# TEENSY_AUDIO_BOARDS.net
KiCad netlist of a schematic drawn in EAGLE
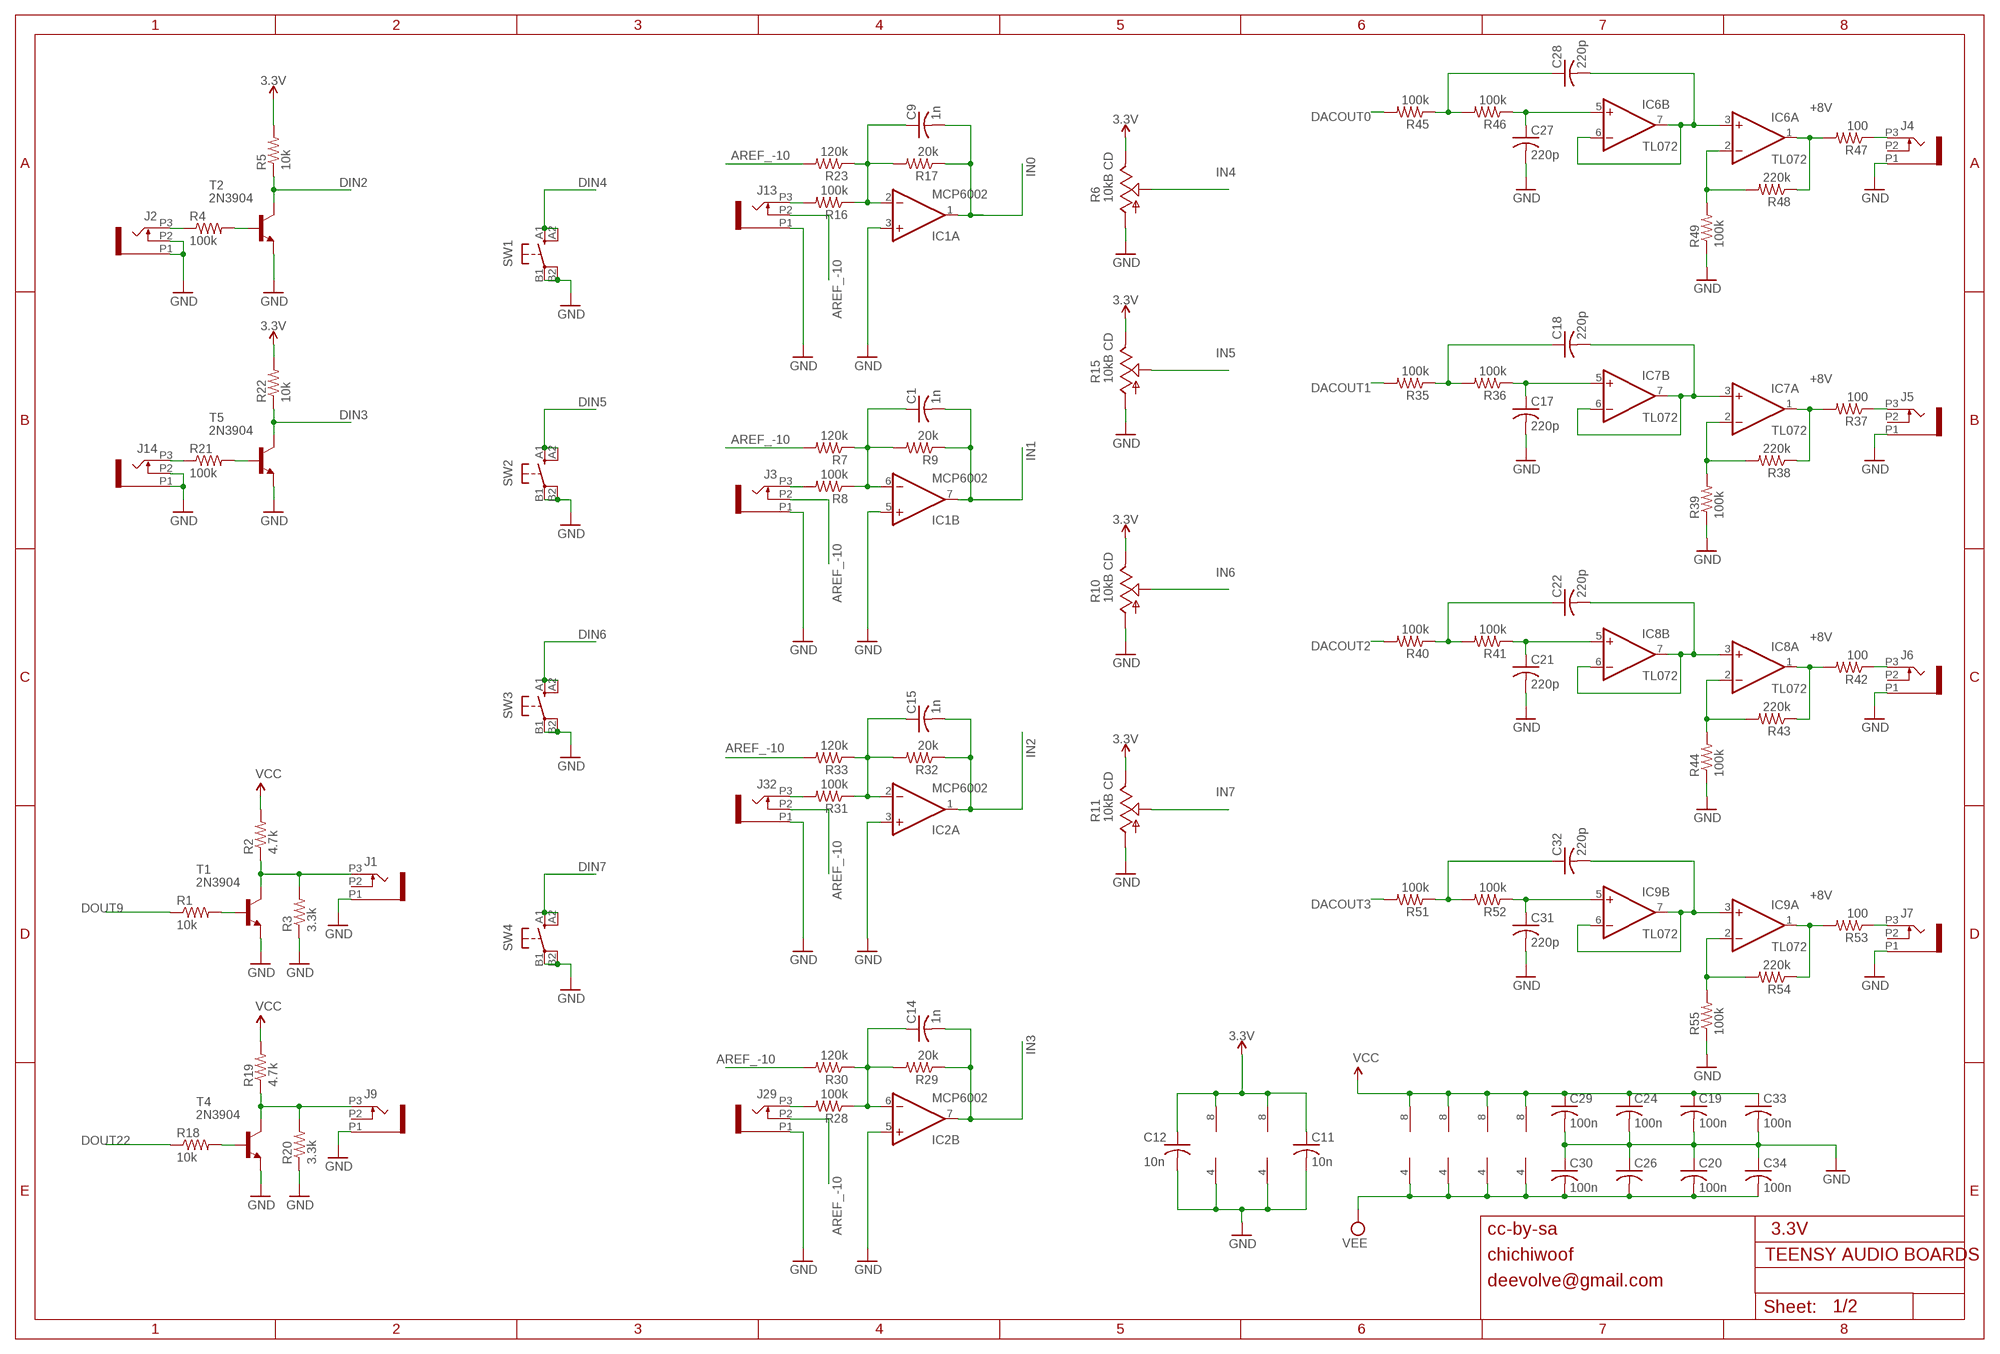
[diagram p0: schematic, sheet 1]
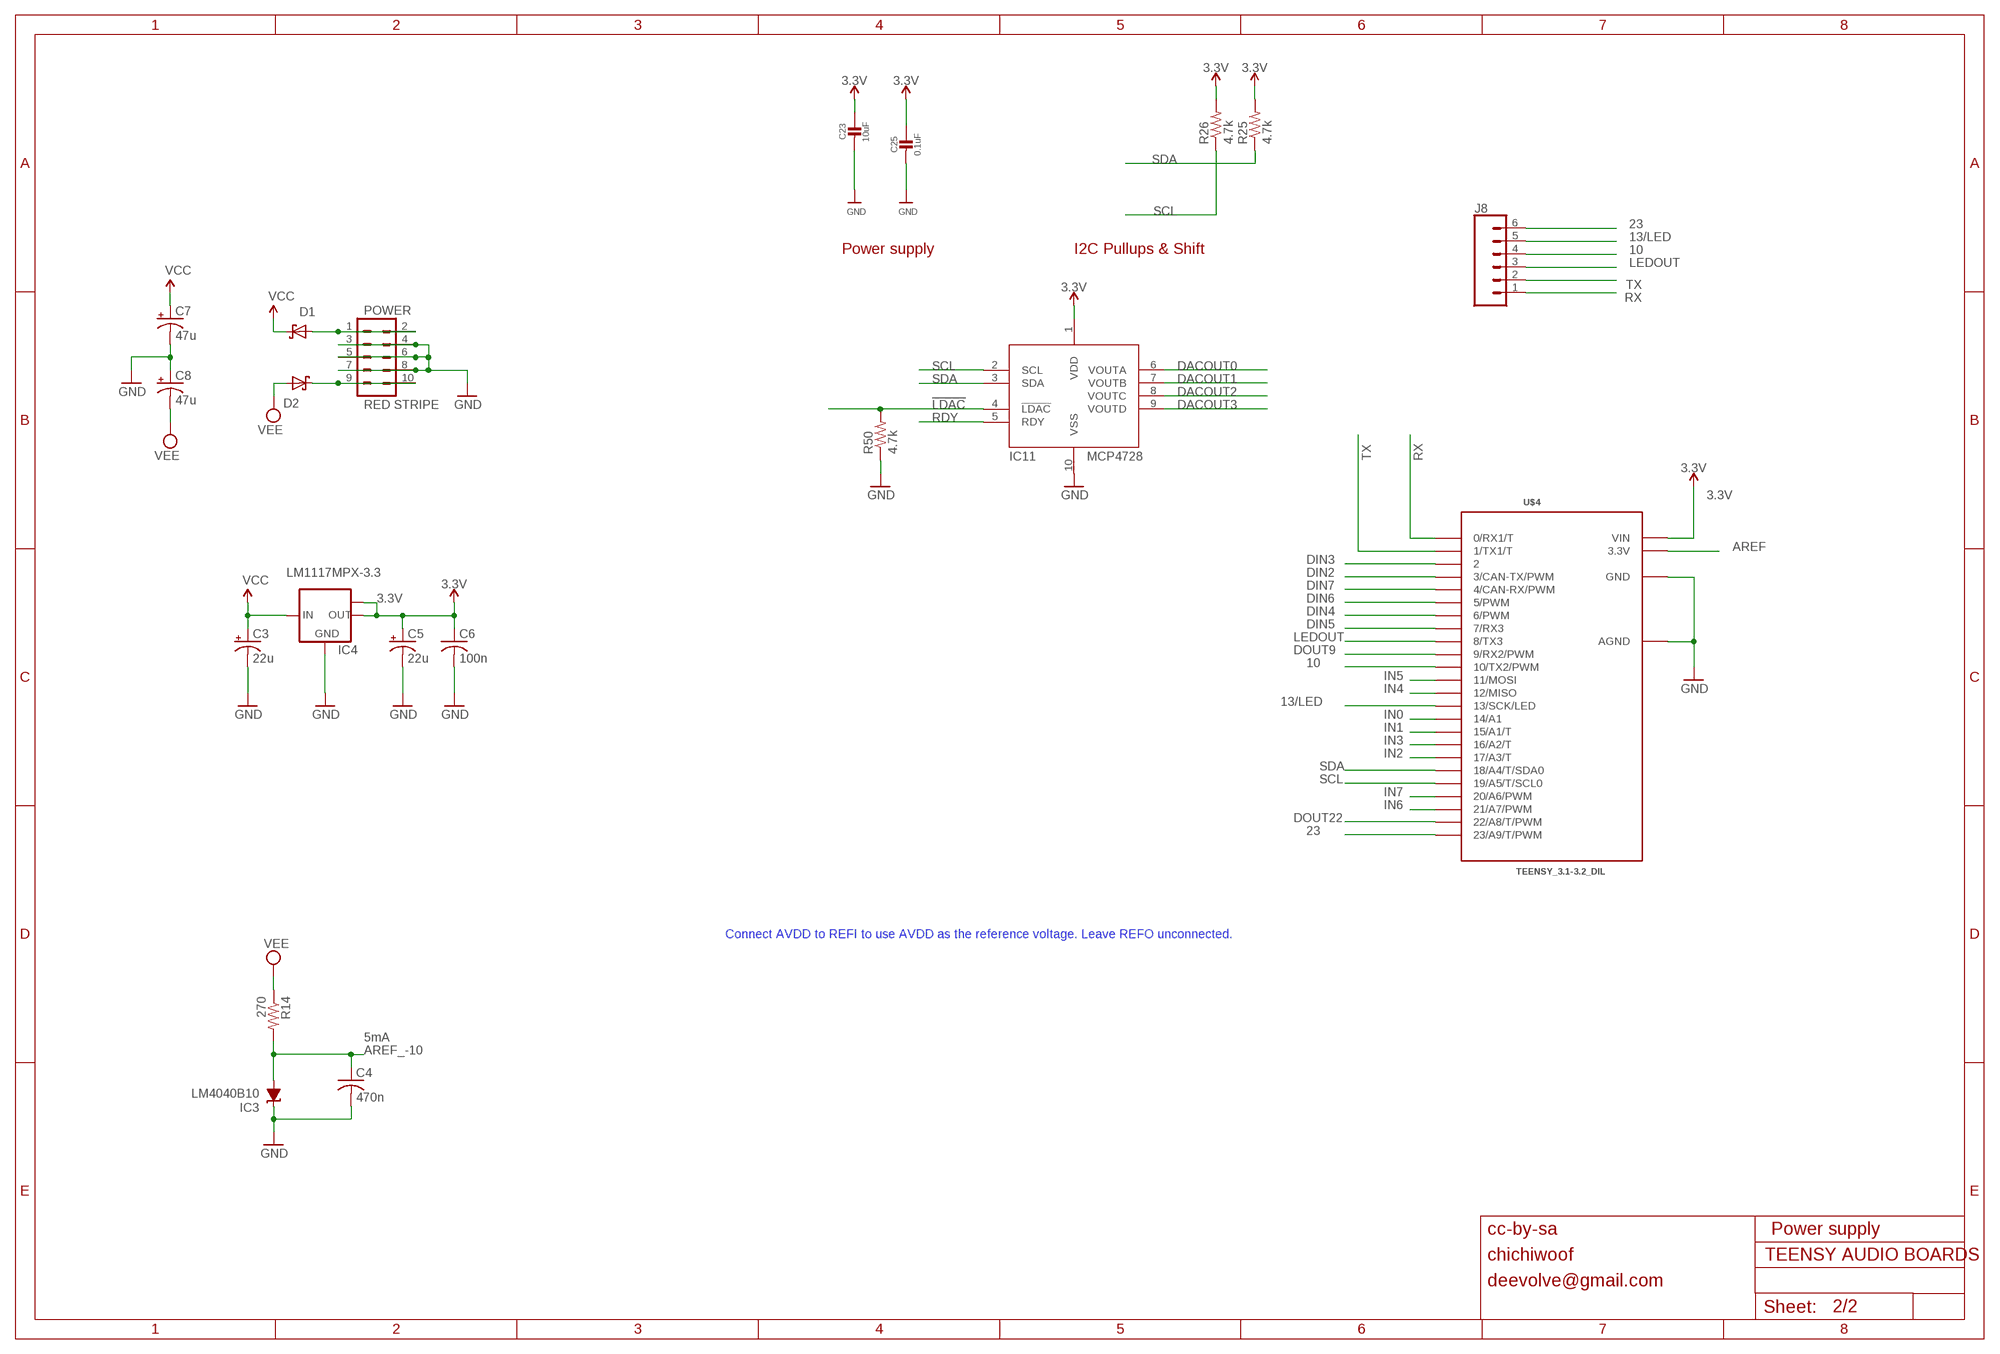
[diagram p1: schematic, sheet 2]

(export (version "E")
  (design (tool "Eeschema 10.0.6"))
  (components
    (comp (ref "C1")
      (value "1n")
      (footprint "eagle-import:C050-025X075")
      (libsource (lib "eagle-import") (part "C-US050-025X075"))
    )
    (comp (ref "C9")
      (value "1n")
      (footprint "eagle-import:C050-025X075")
      (libsource (lib "eagle-import") (part "C-US050-025X075"))
    )
    (comp (ref "C11")
      (value "10n")
      (footprint "eagle-import:C050-025X075")
      (libsource (lib "eagle-import") (part "C-US050-025X075"))
    )
    (comp (ref "C12")
      (value "10n")
      (footprint "eagle-import:C050-025X075")
      (libsource (lib "eagle-import") (part "C-US050-025X075"))
    )
    (comp (ref "C14")
      (value "1n")
      (footprint "eagle-import:C050-025X075")
      (libsource (lib "eagle-import") (part "C-US050-025X075"))
    )
    (comp (ref "C15")
      (value "1n")
      (footprint "eagle-import:C050-025X075")
      (libsource (lib "eagle-import") (part "C-US050-025X075"))
    )
    (comp (ref "C17")
      (value "220p")
      (footprint "eagle-import:C050-025X075")
      (libsource (lib "eagle-import") (part "C-US050-025X075"))
    )
    (comp (ref "C18")
      (value "220p")
      (footprint "eagle-import:C050-025X075")
      (libsource (lib "eagle-import") (part "C-US050-025X075"))
    )
    (comp (ref "C19")
      (value "100n")
      (footprint "eagle-import:C050-025X075")
      (libsource (lib "eagle-import") (part "C-US050-025X075"))
    )
    (comp (ref "C20")
      (value "100n")
      (footprint "eagle-import:C050-025X075")
      (libsource (lib "eagle-import") (part "C-US050-025X075"))
    )
    (comp (ref "C21")
      (value "220p")
      (footprint "eagle-import:C050-025X075")
      (libsource (lib "eagle-import") (part "C-US050-025X075"))
    )
    (comp (ref "C22")
      (value "220p")
      (footprint "eagle-import:C050-025X075")
      (libsource (lib "eagle-import") (part "C-US050-025X075"))
    )
    (comp (ref "C24")
      (value "100n")
      (footprint "eagle-import:C050-025X075")
      (libsource (lib "eagle-import") (part "C-US050-025X075"))
    )
    (comp (ref "C26")
      (value "100n")
      (footprint "eagle-import:C050-025X075")
      (libsource (lib "eagle-import") (part "C-US050-025X075"))
    )
    (comp (ref "C27")
      (value "220p")
      (footprint "eagle-import:C050-025X075")
      (libsource (lib "eagle-import") (part "C-US050-025X075"))
    )
    (comp (ref "C28")
      (value "220p")
      (footprint "eagle-import:C050-025X075")
      (libsource (lib "eagle-import") (part "C-US050-025X075"))
    )
    (comp (ref "C29")
      (value "100n")
      (footprint "eagle-import:C050-025X075")
      (libsource (lib "eagle-import") (part "C-US050-025X075"))
    )
    (comp (ref "C30")
      (value "100n")
      (footprint "eagle-import:C050-025X075")
      (libsource (lib "eagle-import") (part "C-US050-025X075"))
    )
    (comp (ref "C31")
      (value "220p")
      (footprint "eagle-import:C050-025X075")
      (libsource (lib "eagle-import") (part "C-US050-025X075"))
    )
    (comp (ref "C32")
      (value "220p")
      (footprint "eagle-import:C050-025X075")
      (libsource (lib "eagle-import") (part "C-US050-025X075"))
    )
    (comp (ref "C33")
      (value "100n")
      (footprint "eagle-import:C050-025X075")
      (libsource (lib "eagle-import") (part "C-US050-025X075"))
    )
    (comp (ref "C34")
      (value "100n")
      (footprint "eagle-import:C050-025X075")
      (libsource (lib "eagle-import") (part "C-US050-025X075"))
    )
    (comp (ref "IC1")
      (value "MCP6002")
      (footprint "eagle-import:SO08")
      (libsource (lib "eagle-import") (part "TL072D"))
    )
    (comp (ref "IC2")
      (value "MCP6002")
      (footprint "eagle-import:SO08")
      (libsource (lib "eagle-import") (part "TL072D"))
    )
    (comp (ref "IC6")
      (value "TL072")
      (footprint "eagle-import:SO08")
      (libsource (lib "eagle-import") (part "TL072D"))
    )
    (comp (ref "IC7")
      (value "TL072")
      (footprint "eagle-import:SO08")
      (libsource (lib "eagle-import") (part "TL072D"))
    )
    (comp (ref "IC8")
      (value "TL072")
      (footprint "eagle-import:SO08")
      (libsource (lib "eagle-import") (part "TL072D"))
    )
    (comp (ref "IC9")
      (value "TL072")
      (footprint "eagle-import:SO08")
      (libsource (lib "eagle-import") (part "TL072D"))
    )
    (comp (ref "J1")
      (value "PJ301_THONKICONN6")
      (footprint "eagle-import:WQP_PJ_301M6")
      (libsource (lib "eagle-import") (part "PJ301_THONKICONN6"))
    )
    (comp (ref "J2")
      (value "PJ301_THONKICONN6")
      (footprint "eagle-import:WQP_PJ_301M6")
      (libsource (lib "eagle-import") (part "PJ301_THONKICONN6"))
    )
    (comp (ref "J3")
      (value "PJ301_THONKICONN6")
      (footprint "eagle-import:WQP_PJ_301M6")
      (libsource (lib "eagle-import") (part "PJ301_THONKICONN6"))
    )
    (comp (ref "J4")
      (value "PJ301_THONKICONN6")
      (footprint "eagle-import:WQP_PJ_301M6")
      (libsource (lib "eagle-import") (part "PJ301_THONKICONN6"))
    )
    (comp (ref "J5")
      (value "PJ301_THONKICONN6")
      (footprint "eagle-import:WQP_PJ_301M6")
      (libsource (lib "eagle-import") (part "PJ301_THONKICONN6"))
    )
    (comp (ref "J6")
      (value "PJ301_THONKICONN6")
      (footprint "eagle-import:WQP_PJ_301M6")
      (libsource (lib "eagle-import") (part "PJ301_THONKICONN6"))
    )
    (comp (ref "J7")
      (value "PJ301_THONKICONN6")
      (footprint "eagle-import:WQP_PJ_301M6")
      (libsource (lib "eagle-import") (part "PJ301_THONKICONN6"))
    )
    (comp (ref "J9")
      (value "PJ301_THONKICONN6")
      (footprint "eagle-import:WQP_PJ_301M6")
      (libsource (lib "eagle-import") (part "PJ301_THONKICONN6"))
    )
    (comp (ref "J13")
      (value "PJ301_THONKICONN6")
      (footprint "eagle-import:WQP_PJ_301M6")
      (libsource (lib "eagle-import") (part "PJ301_THONKICONN6"))
    )
    (comp (ref "J14")
      (value "PJ301_THONKICONN6")
      (footprint "eagle-import:WQP_PJ_301M6")
      (libsource (lib "eagle-import") (part "PJ301_THONKICONN6"))
    )
    (comp (ref "J29")
      (value "PJ301_THONKICONN6")
      (footprint "eagle-import:WQP_PJ_301M6")
      (libsource (lib "eagle-import") (part "PJ301_THONKICONN6"))
    )
    (comp (ref "J32")
      (value "PJ301_THONKICONN6")
      (footprint "eagle-import:WQP_PJ_301M6")
      (libsource (lib "eagle-import") (part "PJ301_THONKICONN6"))
    )
    (comp (ref "R1")
      (value "10k")
      (footprint "eagle-import:0204_7")
      (libsource (lib "eagle-import") (part "R-US_0204/7"))
    )
    (comp (ref "R2")
      (value "4.7k")
      (footprint "eagle-import:0204_7")
      (libsource (lib "eagle-import") (part "R-US_0204/7"))
    )
    (comp (ref "R3")
      (value "3.3k")
      (footprint "eagle-import:0204_7")
      (libsource (lib "eagle-import") (part "R-US_0204/7"))
    )
    (comp (ref "R4")
      (value "100k")
      (footprint "eagle-import:0204_7")
      (libsource (lib "eagle-import") (part "R-US_0204/7"))
    )
    (comp (ref "R5")
      (value "10k")
      (footprint "eagle-import:0204_7")
      (libsource (lib "eagle-import") (part "R-US_0204/7"))
    )
    (comp (ref "R6")
      (value "10kB CD")
      (footprint "eagle-import:ALPS_POT_VERTICAL_PS")
      (libsource (lib "eagle-import") (part "POT_USVERTICAL_PS"))
    )
    (comp (ref "R7")
      (value "120k")
      (footprint "eagle-import:0204_7")
      (libsource (lib "eagle-import") (part "R-US_0204/7"))
    )
    (comp (ref "R8")
      (value "100k")
      (footprint "eagle-import:0204_7")
      (libsource (lib "eagle-import") (part "R-US_0204/7"))
    )
    (comp (ref "R9")
      (value "20k")
      (footprint "eagle-import:0204_7")
      (libsource (lib "eagle-import") (part "R-US_0204/7"))
    )
    (comp (ref "R10")
      (value "10kB CD")
      (footprint "eagle-import:ALPS_POT_VERTICAL_PS")
      (libsource (lib "eagle-import") (part "POT_USVERTICAL_PS"))
    )
    (comp (ref "R11")
      (value "10kB CD")
      (footprint "eagle-import:ALPS_POT_VERTICAL_PS")
      (libsource (lib "eagle-import") (part "POT_USVERTICAL_PS"))
    )
    (comp (ref "R15")
      (value "10kB CD")
      (footprint "eagle-import:ALPS_POT_VERTICAL_PS")
      (libsource (lib "eagle-import") (part "POT_USVERTICAL_PS"))
    )
    (comp (ref "R16")
      (value "100k")
      (footprint "eagle-import:0204_7")
      (libsource (lib "eagle-import") (part "R-US_0204/7"))
    )
    (comp (ref "R17")
      (value "20k")
      (footprint "eagle-import:0204_7")
      (libsource (lib "eagle-import") (part "R-US_0204/7"))
    )
    (comp (ref "R18")
      (value "10k")
      (footprint "eagle-import:0204_7")
      (libsource (lib "eagle-import") (part "R-US_0204/7"))
    )
    (comp (ref "R19")
      (value "4.7k")
      (footprint "eagle-import:0204_7")
      (libsource (lib "eagle-import") (part "R-US_0204/7"))
    )
    (comp (ref "R20")
      (value "3.3k")
      (footprint "eagle-import:0204_7")
      (libsource (lib "eagle-import") (part "R-US_0204/7"))
    )
    (comp (ref "R21")
      (value "100k")
      (footprint "eagle-import:0204_7")
      (libsource (lib "eagle-import") (part "R-US_0204/7"))
    )
    (comp (ref "R22")
      (value "10k")
      (footprint "eagle-import:0204_7")
      (libsource (lib "eagle-import") (part "R-US_0204/7"))
    )
    (comp (ref "R23")
      (value "120k")
      (footprint "eagle-import:0204_7")
      (libsource (lib "eagle-import") (part "R-US_0204/7"))
    )
    (comp (ref "R28")
      (value "100k")
      (footprint "eagle-import:0204_7")
      (libsource (lib "eagle-import") (part "R-US_0204/7"))
    )
    (comp (ref "R29")
      (value "20k")
      (footprint "eagle-import:0204_7")
      (libsource (lib "eagle-import") (part "R-US_0204/7"))
    )
    (comp (ref "R30")
      (value "120k")
      (footprint "eagle-import:0204_7")
      (libsource (lib "eagle-import") (part "R-US_0204/7"))
    )
    (comp (ref "R31")
      (value "100k")
      (footprint "eagle-import:0204_7")
      (libsource (lib "eagle-import") (part "R-US_0204/7"))
    )
    (comp (ref "R32")
      (value "20k")
      (footprint "eagle-import:0204_7")
      (libsource (lib "eagle-import") (part "R-US_0204/7"))
    )
    (comp (ref "R33")
      (value "120k")
      (footprint "eagle-import:0204_7")
      (libsource (lib "eagle-import") (part "R-US_0204/7"))
    )
    (comp (ref "R35")
      (value "100k")
      (footprint "eagle-import:0204_7")
      (libsource (lib "eagle-import") (part "R-US_0204/7"))
    )
    (comp (ref "R36")
      (value "100k")
      (footprint "eagle-import:0204_7")
      (libsource (lib "eagle-import") (part "R-US_0204/7"))
    )
    (comp (ref "R37")
      (value "100")
      (footprint "eagle-import:0204_7")
      (libsource (lib "eagle-import") (part "R-US_0204/7"))
    )
    (comp (ref "R38")
      (value "220k")
      (footprint "eagle-import:0204_7")
      (libsource (lib "eagle-import") (part "R-US_0204/7"))
    )
    (comp (ref "R39")
      (value "100k")
      (footprint "eagle-import:0204_7")
      (libsource (lib "eagle-import") (part "R-US_0204/7"))
    )
    (comp (ref "R40")
      (value "100k")
      (footprint "eagle-import:0204_7")
      (libsource (lib "eagle-import") (part "R-US_0204/7"))
    )
    (comp (ref "R41")
      (value "100k")
      (footprint "eagle-import:0204_7")
      (libsource (lib "eagle-import") (part "R-US_0204/7"))
    )
    (comp (ref "R42")
      (value "100")
      (footprint "eagle-import:0204_7")
      (libsource (lib "eagle-import") (part "R-US_0204/7"))
    )
    (comp (ref "R43")
      (value "220k")
      (footprint "eagle-import:0204_7")
      (libsource (lib "eagle-import") (part "R-US_0204/7"))
    )
    (comp (ref "R44")
      (value "100k")
      (footprint "eagle-import:0204_7")
      (libsource (lib "eagle-import") (part "R-US_0204/7"))
    )
    (comp (ref "R45")
      (value "100k")
      (footprint "eagle-import:0204_7")
      (libsource (lib "eagle-import") (part "R-US_0204/7"))
    )
    (comp (ref "R46")
      (value "100k")
      (footprint "eagle-import:0204_7")
      (libsource (lib "eagle-import") (part "R-US_0204/7"))
    )
    (comp (ref "R47")
      (value "100")
      (footprint "eagle-import:0204_7")
      (libsource (lib "eagle-import") (part "R-US_0204/7"))
    )
    (comp (ref "R48")
      (value "220k")
      (footprint "eagle-import:0204_7")
      (libsource (lib "eagle-import") (part "R-US_0204/7"))
    )
    (comp (ref "R49")
      (value "100k")
      (footprint "eagle-import:0204_7")
      (libsource (lib "eagle-import") (part "R-US_0204/7"))
    )
    (comp (ref "R51")
      (value "100k")
      (footprint "eagle-import:0204_7")
      (libsource (lib "eagle-import") (part "R-US_0204/7"))
    )
    (comp (ref "R52")
      (value "100k")
      (footprint "eagle-import:0204_7")
      (libsource (lib "eagle-import") (part "R-US_0204/7"))
    )
    (comp (ref "R53")
      (value "100")
      (footprint "eagle-import:0204_7")
      (libsource (lib "eagle-import") (part "R-US_0204/7"))
    )
    (comp (ref "R54")
      (value "220k")
      (footprint "eagle-import:0204_7")
      (libsource (lib "eagle-import") (part "R-US_0204/7"))
    )
    (comp (ref "R55")
      (value "100k")
      (footprint "eagle-import:0204_7")
      (libsource (lib "eagle-import") (part "R-US_0204/7"))
    )
    (comp (ref "SW1")
      (value "D6R")
      (footprint "eagle-import:D6R")
      (libsource (lib "eagle-import") (part "D6R"))
    )
    (comp (ref "SW2")
      (value "D6R")
      (footprint "eagle-import:D6R")
      (libsource (lib "eagle-import") (part "D6R"))
    )
    (comp (ref "SW3")
      (value "D6R")
      (footprint "eagle-import:D6R")
      (libsource (lib "eagle-import") (part "D6R"))
    )
    (comp (ref "SW4")
      (value "D6R")
      (footprint "eagle-import:D6R")
      (libsource (lib "eagle-import") (part "D6R"))
    )
    (comp (ref "T1")
      (value "2N3904")
      (footprint "eagle-import:TO92")
      (libsource (lib "eagle-import") (part "2N3904"))
    )
    (comp (ref "T2")
      (value "2N3904")
      (footprint "eagle-import:TO92")
      (libsource (lib "eagle-import") (part "2N3904"))
    )
    (comp (ref "T4")
      (value "2N3904")
      (footprint "eagle-import:TO92")
      (libsource (lib "eagle-import") (part "2N3904"))
    )
    (comp (ref "T5")
      (value "2N3904")
      (footprint "eagle-import:TO92")
      (libsource (lib "eagle-import") (part "2N3904"))
    )
    (comp (ref "C3")
      (value "22u")
      (footprint "eagle-import:E2,5-7")
      (libsource (lib "eagle-import") (part "CPOL-USE2.5-7"))
    )
    (comp (ref "C4")
      (value "470n")
      (footprint "eagle-import:C050-025X075")
      (libsource (lib "eagle-import") (part "C-US050-025X075"))
    )
    (comp (ref "C5")
      (value "22u")
      (footprint "eagle-import:E2,5-7")
      (libsource (lib "eagle-import") (part "CPOL-USE2.5-7"))
    )
    (comp (ref "C6")
      (value "100n")
      (footprint "eagle-import:C050-025X075")
      (libsource (lib "eagle-import") (part "C-US050-025X075"))
    )
    (comp (ref "C7")
      (value "47u")
      (footprint "eagle-import:E2,5-7")
      (libsource (lib "eagle-import") (part "CPOL-USE2.5-7"))
    )
    (comp (ref "C8")
      (value "47u")
      (footprint "eagle-import:E2,5-7")
      (libsource (lib "eagle-import") (part "CPOL-USE2.5-7"))
    )
    (comp (ref "C23")
      (value "10uF")
      (footprint "eagle-import:0805-NO")
      (libsource (lib "eagle-import") (part "CAP_CERAMIC0805-NOOUTLINE"))
    )
    (comp (ref "C25")
      (value "0.1uF")
      (footprint "eagle-import:0603-NO")
      (libsource (lib "eagle-import") (part "CAP_CERAMIC0603_NO"))
    )
    (comp (ref "D1")
      (value "1N5819")
      (footprint "eagle-import:DO41-10")
      (libsource (lib "eagle-import") (part "SCHOTTKY-DIODEDO41"))
    )
    (comp (ref "D2")
      (value "1N5819")
      (footprint "eagle-import:DO41-10")
      (libsource (lib "eagle-import") (part "SCHOTTKY-DIODEDO41"))
    )
    (comp (ref "IC3")
      (value "LM4040B10")
      (footprint "eagle-import:DBZ_R-PDSO-G3")
      (libsource (lib "eagle-import") (part "LM4041DBZB12"))
    )
    (comp (ref "IC4")
      (value "LM1117MPX-3.3")
      (footprint "eagle-import:SOT223")
      (libsource (lib "eagle-import") (part "LM1117MPX-3.3"))
    )
    (comp (ref "IC11")
      (value "MCP4728")
      (footprint "eagle-import:MSOP10")
      (libsource (lib "eagle-import") (part "MCP4728"))
    )
    (comp (ref "J8")
      (value "CONN_06SILK_FEMALE_PTH")
      (footprint "eagle-import:1X06")
      (libsource (lib "eagle-import") (part "CONN_06SILK_FEMALE_PTH"))
    )
    (comp (ref "POWER")
      (value "RED STRIPE")
      (footprint "eagle-import:AVR_ICSP")
      (libsource (lib "eagle-import") (part "M05X2PTH"))
    )
    (comp (ref "R14")
      (value "270")
      (footprint "eagle-import:0204_7")
      (libsource (lib "eagle-import") (part "R-US_0204/7"))
    )
    (comp (ref "R25")
      (value "4.7k")
      (footprint "eagle-import:0204_7")
      (libsource (lib "eagle-import") (part "R-US_0204/7"))
    )
    (comp (ref "R26")
      (value "4.7k")
      (footprint "eagle-import:0204_7")
      (libsource (lib "eagle-import") (part "R-US_0204/7"))
    )
    (comp (ref "R50")
      (value "4.7k")
      (footprint "eagle-import:0204_7")
      (libsource (lib "eagle-import") (part "R-US_0204/7"))
    )
    (comp (ref "U$4")
      (value "TEENSY_3.1-3.2_DIL")
      (footprint "eagle-import:TEENSY_3.0-3.2&LC_DIL")
      (libsource (lib "eagle-import") (part "TEENSY_3.1-3.2_DIL"))
    )
  )
  (nets
    (net (code "1") (name "3.3V") (class "Default")
      (node (ref "C11") (pin "1") (pinfunction "1_1") (pintype "passive"))
      (node (ref "C12") (pin "1") (pinfunction "1_1") (pintype "passive"))
      (node (ref "C23") (pin "1") (pinfunction "1_1") (pintype "passive"))
      (node (ref "C25") (pin "1") (pinfunction "1_1") (pintype "passive"))
      (node (ref "C5") (pin "+") (pinfunction "+_+") (pintype "passive"))
      (node (ref "C6") (pin "1") (pinfunction "1_1") (pintype "passive"))
      (node (ref "IC1") (pin "8") (pinfunction "V+_8") (pintype "power_in"))
      (node (ref "IC11") (pin "1") (pinfunction "VDD_1") (pintype "power_in"))
      (node (ref "IC2") (pin "8") (pinfunction "V+_8") (pintype "power_in"))
      (node (ref "IC4") (pin "2") (pinfunction "OUT_2") (pintype "passive"))
      (node (ref "IC4") (pin "TAB") (pinfunction "OUT1_TAB") (pintype "passive"))
      (node (ref "R10") (pin "P$1") (pinfunction "E_P$1") (pintype "passive"))
      (node (ref "R11") (pin "P$1") (pinfunction "E_P$1") (pintype "passive"))
      (node (ref "R15") (pin "P$1") (pinfunction "E_P$1") (pintype "passive"))
      (node (ref "R22") (pin "2") (pinfunction "2_2") (pintype "passive"))
      (node (ref "R25") (pin "2") (pinfunction "2_2") (pintype "passive"))
      (node (ref "R26") (pin "2") (pinfunction "2_2") (pintype "passive"))
      (node (ref "R5") (pin "2") (pinfunction "2_2") (pintype "passive"))
      (node (ref "R6") (pin "P$1") (pinfunction "E_P$1") (pintype "passive"))
      (node (ref "U$4") (pin "VIN") (pinfunction "VIN_VIN") (pintype "power_in"))
    )
    (net (code "2") (name "10") (class "Default")
      (node (ref "J8") (pin "4") (pinfunction "4_4") (pintype "passive"))
      (node (ref "U$4") (pin "10") (pinfunction "10/TX2/PWM_10") (pintype "bidirectional"))
    )
    (net (code "3") (name "13{slash}LED") (class "Default")
      (node (ref "J8") (pin "5") (pinfunction "5_5") (pintype "passive"))
      (node (ref "U$4") (pin "13") (pinfunction "13/SCK/LED_13") (pintype "bidirectional"))
    )
    (net (code "4") (name "23") (class "Default")
      (node (ref "J8") (pin "6") (pinfunction "6_6") (pintype "passive"))
      (node (ref "U$4") (pin "23/A9") (pinfunction "23/A9/T/PWM_23/A9") (pintype "bidirectional"))
    )
    (net (code "5") (name "AREF") (class "Default")
      (node (ref "U$4") (pin "3.3V") (pinfunction "3.3V_3.3V") (pintype "power_in"))
    )
    (net (code "6") (name "AREF_-10") (class "Default")
      (node (ref "C4") (pin "1") (pinfunction "1_1") (pintype "passive"))
      (node (ref "IC3") (pin "2") (pinfunction "A_2") (pintype "passive"))
      (node (ref "J13") (pin "P2") (pinfunction "2_P2") (pintype "passive"))
      (node (ref "J29") (pin "P2") (pinfunction "2_P2") (pintype "passive"))
      (node (ref "J3") (pin "P2") (pinfunction "2_P2") (pintype "passive"))
      (node (ref "J32") (pin "P2") (pinfunction "2_P2") (pintype "passive"))
      (node (ref "R14") (pin "2") (pinfunction "2_2") (pintype "passive"))
      (node (ref "R23") (pin "2") (pinfunction "2_2") (pintype "passive"))
      (node (ref "R30") (pin "2") (pinfunction "2_2") (pintype "passive"))
      (node (ref "R33") (pin "2") (pinfunction "2_2") (pintype "passive"))
      (node (ref "R7") (pin "2") (pinfunction "2_2") (pintype "passive"))
    )
    (net (code "7") (name "DACOUT0") (class "Default")
      (node (ref "IC11") (pin "6") (pinfunction "VOUTA_6") (pintype "output"))
      (node (ref "R45") (pin "2") (pinfunction "2_2") (pintype "passive"))
    )
    (net (code "8") (name "DACOUT1") (class "Default")
      (node (ref "IC11") (pin "7") (pinfunction "VOUTB_7") (pintype "output"))
      (node (ref "R35") (pin "2") (pinfunction "2_2") (pintype "passive"))
    )
    (net (code "9") (name "DACOUT2") (class "Default")
      (node (ref "IC11") (pin "8") (pinfunction "VOUTC_8") (pintype "output"))
      (node (ref "R40") (pin "2") (pinfunction "2_2") (pintype "passive"))
    )
    (net (code "10") (name "DACOUT3") (class "Default")
      (node (ref "IC11") (pin "9") (pinfunction "VOUTD_9") (pintype "output"))
      (node (ref "R51") (pin "2") (pinfunction "2_2") (pintype "passive"))
    )
    (net (code "11") (name "DIN2") (class "Default")
      (node (ref "R5") (pin "1") (pinfunction "1_1") (pintype "passive"))
      (node (ref "T2") (pin "1") (pinfunction "C_1") (pintype "passive"))
      (node (ref "U$4") (pin "3") (pinfunction "3/CAN-TX/PWM_3") (pintype "bidirectional"))
    )
    (net (code "12") (name "DIN3") (class "Default")
      (node (ref "R22") (pin "1") (pinfunction "1_1") (pintype "passive"))
      (node (ref "T5") (pin "1") (pinfunction "C_1") (pintype "passive"))
      (node (ref "U$4") (pin "2") (pinfunction "2_2") (pintype "bidirectional"))
    )
    (net (code "13") (name "DIN4") (class "Default")
      (node (ref "SW1") (pin "A1") (pinfunction "S_A1") (pintype "passive"))
      (node (ref "SW1") (pin "A2") (pinfunction "S1_A2") (pintype "passive"))
      (node (ref "U$4") (pin "6") (pinfunction "6/PWM_6") (pintype "bidirectional"))
    )
    (net (code "14") (name "DIN5") (class "Default")
      (node (ref "SW2") (pin "A1") (pinfunction "S_A1") (pintype "passive"))
      (node (ref "SW2") (pin "A2") (pinfunction "S1_A2") (pintype "passive"))
      (node (ref "U$4") (pin "7") (pinfunction "7/RX3_7") (pintype "bidirectional"))
    )
    (net (code "15") (name "DIN6") (class "Default")
      (node (ref "SW3") (pin "A1") (pinfunction "S_A1") (pintype "passive"))
      (node (ref "SW3") (pin "A2") (pinfunction "S1_A2") (pintype "passive"))
      (node (ref "U$4") (pin "5") (pinfunction "5/PWM_5") (pintype "bidirectional"))
    )
    (net (code "16") (name "DIN7") (class "Default")
      (node (ref "SW4") (pin "A1") (pinfunction "S_A1") (pintype "passive"))
      (node (ref "SW4") (pin "A2") (pinfunction "S1_A2") (pintype "passive"))
      (node (ref "U$4") (pin "4") (pinfunction "4/CAN-RX/PWM_4") (pintype "bidirectional"))
    )
    (net (code "17") (name "DOUT9") (class "Default")
      (node (ref "R1") (pin "1") (pinfunction "1_1") (pintype "passive"))
      (node (ref "U$4") (pin "9") (pinfunction "9/RX2/PWM_9") (pintype "bidirectional"))
    )
    (net (code "18") (name "DOUT22") (class "Default")
      (node (ref "R18") (pin "1") (pinfunction "1_1") (pintype "passive"))
      (node (ref "U$4") (pin "22/A8") (pinfunction "22/A8/T/PWM_22/A8") (pintype "bidirectional"))
    )
    (net (code "19") (name "GND") (class "Default")
      (node (ref "C11") (pin "2") (pinfunction "2_2") (pintype "passive"))
      (node (ref "C12") (pin "2") (pinfunction "2_2") (pintype "passive"))
      (node (ref "C17") (pin "2") (pinfunction "2_2") (pintype "passive"))
      (node (ref "C19") (pin "2") (pinfunction "2_2") (pintype "passive"))
      (node (ref "C20") (pin "1") (pinfunction "1_1") (pintype "passive"))
      (node (ref "C21") (pin "2") (pinfunction "2_2") (pintype "passive"))
      (node (ref "C23") (pin "2") (pinfunction "2_2") (pintype "passive"))
      (node (ref "C24") (pin "2") (pinfunction "2_2") (pintype "passive"))
      (node (ref "C25") (pin "2") (pinfunction "2_2") (pintype "passive"))
      (node (ref "C26") (pin "1") (pinfunction "1_1") (pintype "passive"))
      (node (ref "C27") (pin "2") (pinfunction "2_2") (pintype "passive"))
      (node (ref "C29") (pin "2") (pinfunction "2_2") (pintype "passive"))
      (node (ref "C3") (pin "-") (pinfunction "-_-") (pintype "passive"))
      (node (ref "C30") (pin "1") (pinfunction "1_1") (pintype "passive"))
      (node (ref "C31") (pin "2") (pinfunction "2_2") (pintype "passive"))
      (node (ref "C33") (pin "2") (pinfunction "2_2") (pintype "passive"))
      (node (ref "C34") (pin "1") (pinfunction "1_1") (pintype "passive"))
      (node (ref "C4") (pin "2") (pinfunction "2_2") (pintype "passive"))
      (node (ref "C5") (pin "-") (pinfunction "-_-") (pintype "passive"))
      (node (ref "C6") (pin "2") (pinfunction "2_2") (pintype "passive"))
      (node (ref "C7") (pin "-") (pinfunction "-_-") (pintype "passive"))
      (node (ref "C8") (pin "+") (pinfunction "+_+") (pintype "passive"))
      (node (ref "IC1") (pin "3") (pinfunction "+IN_3") (pintype "input"))
      (node (ref "IC1") (pin "4") (pinfunction "V-_4") (pintype "power_in"))
      (node (ref "IC1") (pin "5") (pinfunction "+IN_5") (pintype "input"))
      (node (ref "IC11") (pin "10") (pinfunction "VSS_10") (pintype "power_in"))
      (node (ref "IC2") (pin "3") (pinfunction "+IN_3") (pintype "input"))
      (node (ref "IC2") (pin "4") (pinfunction "V-_4") (pintype "power_in"))
      (node (ref "IC2") (pin "5") (pinfunction "+IN_5") (pintype "input"))
      (node (ref "IC3") (pin "1") (pinfunction "C_1") (pintype "passive"))
      (node (ref "IC4") (pin "1") (pinfunction "GND_1") (pintype "input"))
      (node (ref "J1") (pin "P1") (pinfunction "1_P1") (pintype "passive"))
      (node (ref "J13") (pin "P1") (pinfunction "1_P1") (pintype "passive"))
      (node (ref "J14") (pin "P1") (pinfunction "1_P1") (pintype "passive"))
      (node (ref "J14") (pin "P2") (pinfunction "2_P2") (pintype "passive"))
      (node (ref "J2") (pin "P1") (pinfunction "1_P1") (pintype "passive"))
      (node (ref "J2") (pin "P2") (pinfunction "2_P2") (pintype "passive"))
      (node (ref "J29") (pin "P1") (pinfunction "1_P1") (pintype "passive"))
      (node (ref "J3") (pin "P1") (pinfunction "1_P1") (pintype "passive"))
      (node (ref "J32") (pin "P1") (pinfunction "1_P1") (pintype "passive"))
      (node (ref "J4") (pin "P1") (pinfunction "1_P1") (pintype "passive"))
      (node (ref "J5") (pin "P1") (pinfunction "1_P1") (pintype "passive"))
      (node (ref "J6") (pin "P1") (pinfunction "1_P1") (pintype "passive"))
      (node (ref "J7") (pin "P1") (pinfunction "1_P1") (pintype "passive"))
      (node (ref "J9") (pin "P1") (pinfunction "1_P1") (pintype "passive"))
      (node (ref "POWER") (pin "3") (pinfunction "3_3") (pintype "passive"))
      (node (ref "POWER") (pin "4") (pinfunction "4_4") (pintype "passive"))
      (node (ref "POWER") (pin "5") (pinfunction "5_5") (pintype "passive"))
      (node (ref "POWER") (pin "6") (pinfunction "6_6") (pintype "passive"))
      (node (ref "POWER") (pin "7") (pinfunction "7_7") (pintype "passive"))
      (node (ref "POWER") (pin "8") (pinfunction "8_8") (pintype "passive"))
      (node (ref "R10") (pin "P$3") (pinfunction "A_P$3") (pintype "passive"))
      (node (ref "R11") (pin "P$3") (pinfunction "A_P$3") (pintype "passive"))
      (node (ref "R15") (pin "P$3") (pinfunction "A_P$3") (pintype "passive"))
      (node (ref "R20") (pin "1") (pinfunction "1_1") (pintype "passive"))
      (node (ref "R3") (pin "1") (pinfunction "1_1") (pintype "passive"))
      (node (ref "R39") (pin "1") (pinfunction "1_1") (pintype "passive"))
      (node (ref "R44") (pin "1") (pinfunction "1_1") (pintype "passive"))
      (node (ref "R49") (pin "1") (pinfunction "1_1") (pintype "passive"))
      (node (ref "R50") (pin "1") (pinfunction "1_1") (pintype "passive"))
      (node (ref "R55") (pin "1") (pinfunction "1_1") (pintype "passive"))
      (node (ref "R6") (pin "P$3") (pinfunction "A_P$3") (pintype "passive"))
      (node (ref "SW1") (pin "B1") (pinfunction "P_B1") (pintype "passive"))
      (node (ref "SW1") (pin "B2") (pinfunction "P1_B2") (pintype "passive"))
      (node (ref "SW2") (pin "B1") (pinfunction "P_B1") (pintype "passive"))
      (node (ref "SW2") (pin "B2") (pinfunction "P1_B2") (pintype "passive"))
      (node (ref "SW3") (pin "B1") (pinfunction "P_B1") (pintype "passive"))
      (node (ref "SW3") (pin "B2") (pinfunction "P1_B2") (pintype "passive"))
      (node (ref "SW4") (pin "B1") (pinfunction "P_B1") (pintype "passive"))
      (node (ref "SW4") (pin "B2") (pinfunction "P1_B2") (pintype "passive"))
      (node (ref "T1") (pin "3") (pinfunction "E_3") (pintype "passive"))
      (node (ref "T2") (pin "3") (pinfunction "E_3") (pintype "passive"))
      (node (ref "T4") (pin "3") (pinfunction "E_3") (pintype "passive"))
      (node (ref "T5") (pin "3") (pinfunction "E_3") (pintype "passive"))
      (node (ref "U$4") (pin "AGND") (pinfunction "AGND_AGND") (pintype "power_in"))
      (node (ref "U$4") (pin "GND") (pinfunction "GND_GND") (pintype "power_in"))
    )
    (net (code "20") (name "IN0") (class "Default")
      (node (ref "C9") (pin "2") (pinfunction "2_2") (pintype "passive"))
      (node (ref "IC1") (pin "1") (pinfunction "OUT_1") (pintype "output"))
      (node (ref "R17") (pin "1") (pinfunction "1_1") (pintype "passive"))
      (node (ref "U$4") (pin "14/A0") (pinfunction "14/A1_14/A0") (pintype "bidirectional"))
    )
    (net (code "21") (name "IN1") (class "Default")
      (node (ref "C1") (pin "2") (pinfunction "2_2") (pintype "passive"))
      (node (ref "IC1") (pin "7") (pinfunction "OUT_7") (pintype "output"))
      (node (ref "R9") (pin "1") (pinfunction "1_1") (pintype "passive"))
      (node (ref "U$4") (pin "15/A1") (pinfunction "15/A1/T_15/A1") (pintype "bidirectional"))
    )
    (net (code "22") (name "IN2") (class "Default")
      (node (ref "C15") (pin "2") (pinfunction "2_2") (pintype "passive"))
      (node (ref "IC2") (pin "1") (pinfunction "OUT_1") (pintype "output"))
      (node (ref "R32") (pin "1") (pinfunction "1_1") (pintype "passive"))
      (node (ref "U$4") (pin "17/A3") (pinfunction "17/A3/T_17/A3") (pintype "bidirectional"))
    )
    (net (code "23") (name "IN3") (class "Default")
      (node (ref "C14") (pin "2") (pinfunction "2_2") (pintype "passive"))
      (node (ref "IC2") (pin "7") (pinfunction "OUT_7") (pintype "output"))
      (node (ref "R29") (pin "1") (pinfunction "1_1") (pintype "passive"))
      (node (ref "U$4") (pin "16/A2") (pinfunction "16/A2/T_16/A2") (pintype "bidirectional"))
    )
    (net (code "24") (name "IN4") (class "Default")
      (node (ref "R6") (pin "P$2") (pinfunction "S_P$2") (pintype "passive"))
      (node (ref "U$4") (pin "12") (pinfunction "12/MISO_12") (pintype "bidirectional"))
    )
    (net (code "25") (name "IN5") (class "Default")
      (node (ref "R15") (pin "P$2") (pinfunction "S_P$2") (pintype "passive"))
      (node (ref "U$4") (pin "11") (pinfunction "11/MOSI_11") (pintype "bidirectional"))
    )
    (net (code "26") (name "IN6") (class "Default")
      (node (ref "R10") (pin "P$2") (pinfunction "S_P$2") (pintype "passive"))
      (node (ref "U$4") (pin "21/A7") (pinfunction "21/A7/PWM_21/A7") (pintype "bidirectional"))
    )
    (net (code "27") (name "IN7") (class "Default")
      (node (ref "R11") (pin "P$2") (pinfunction "S_P$2") (pintype "passive"))
      (node (ref "U$4") (pin "20/A6") (pinfunction "20/A6/PWM_20/A6") (pintype "bidirectional"))
    )
    (net (code "28") (name "LEDOUT") (class "Default")
      (node (ref "J8") (pin "3") (pinfunction "3_3") (pintype "passive"))
      (node (ref "U$4") (pin "8") (pinfunction "8/TX3_8") (pintype "bidirectional"))
    )
    (net (code "29") (name "Net-(C18-Pad1)") (class "Default")
      (node (ref "C18") (pin "1") (pinfunction "1_1") (pintype "passive"))
      (node (ref "R35") (pin "1") (pinfunction "1_1") (pintype "passive"))
      (node (ref "R36") (pin "2") (pinfunction "2_2") (pintype "passive"))
    )
    (net (code "30") (name "Net-(C22-Pad1)") (class "Default")
      (node (ref "C22") (pin "1") (pinfunction "1_1") (pintype "passive"))
      (node (ref "R40") (pin "1") (pinfunction "1_1") (pintype "passive"))
      (node (ref "R41") (pin "2") (pinfunction "2_2") (pintype "passive"))
    )
    (net (code "31") (name "Net-(C28-Pad1)") (class "Default")
      (node (ref "C28") (pin "1") (pinfunction "1_1") (pintype "passive"))
      (node (ref "R45") (pin "1") (pinfunction "1_1") (pintype "passive"))
      (node (ref "R46") (pin "2") (pinfunction "2_2") (pintype "passive"))
    )
    (net (code "32") (name "Net-(C32-Pad1)") (class "Default")
      (node (ref "C32") (pin "1") (pinfunction "1_1") (pintype "passive"))
      (node (ref "R51") (pin "1") (pinfunction "1_1") (pintype "passive"))
      (node (ref "R52") (pin "2") (pinfunction "2_2") (pintype "passive"))
    )
    (net (code "33") (name "Net-(D1-PadA)") (class "Default")
      (node (ref "D1") (pin "A") (pinfunction "A_A") (pintype "passive"))
      (node (ref "POWER") (pin "1") (pinfunction "1_1") (pintype "passive"))
      (node (ref "POWER") (pin "2") (pinfunction "2_2") (pintype "passive"))
    )
    (net (code "34") (name "Net-(D2-PadC)") (class "Default")
      (node (ref "D2") (pin "C") (pinfunction "C_C") (pintype "passive"))
      (node (ref "POWER") (pin "10") (pinfunction "10_10") (pintype "passive"))
      (node (ref "POWER") (pin "9") (pinfunction "9_9") (pintype "passive"))
    )
    (net (code "35") (name "Net-(IC1A--IN)") (class "Default")
      (node (ref "C9") (pin "1") (pinfunction "1_1") (pintype "passive"))
      (node (ref "IC1") (pin "2") (pinfunction "-IN_2") (pintype "input"))
      (node (ref "R16") (pin "1") (pinfunction "1_1") (pintype "passive"))
      (node (ref "R17") (pin "2") (pinfunction "2_2") (pintype "passive"))
      (node (ref "R23") (pin "1") (pinfunction "1_1") (pintype "passive"))
    )
    (net (code "36") (name "Net-(IC1B--IN)") (class "Default")
      (node (ref "C1") (pin "1") (pinfunction "1_1") (pintype "passive"))
      (node (ref "IC1") (pin "6") (pinfunction "-IN_6") (pintype "input"))
      (node (ref "R7") (pin "1") (pinfunction "1_1") (pintype "passive"))
      (node (ref "R8") (pin "1") (pinfunction "1_1") (pintype "passive"))
      (node (ref "R9") (pin "2") (pinfunction "2_2") (pintype "passive"))
    )
    (net (code "37") (name "Net-(IC2A--IN)") (class "Default")
      (node (ref "C15") (pin "1") (pinfunction "1_1") (pintype "passive"))
      (node (ref "IC2") (pin "2") (pinfunction "-IN_2") (pintype "input"))
      (node (ref "R31") (pin "1") (pinfunction "1_1") (pintype "passive"))
      (node (ref "R32") (pin "2") (pinfunction "2_2") (pintype "passive"))
      (node (ref "R33") (pin "1") (pinfunction "1_1") (pintype "passive"))
    )
    (net (code "38") (name "Net-(IC2B--IN)") (class "Default")
      (node (ref "C14") (pin "1") (pinfunction "1_1") (pintype "passive"))
      (node (ref "IC2") (pin "6") (pinfunction "-IN_6") (pintype "input"))
      (node (ref "R28") (pin "1") (pinfunction "1_1") (pintype "passive"))
      (node (ref "R29") (pin "2") (pinfunction "2_2") (pintype "passive"))
      (node (ref "R30") (pin "1") (pinfunction "1_1") (pintype "passive"))
    )
    (net (code "39") (name "Net-(IC6A-+IN)") (class "Default")
      (node (ref "C28") (pin "2") (pinfunction "2_2") (pintype "passive"))
      (node (ref "IC6") (pin "3") (pinfunction "+IN_3") (pintype "input"))
      (node (ref "IC6") (pin "6") (pinfunction "-IN_6") (pintype "input"))
      (node (ref "IC6") (pin "7") (pinfunction "OUT_7") (pintype "output"))
    )
    (net (code "40") (name "Net-(IC6A--IN)") (class "Default")
      (node (ref "IC6") (pin "2") (pinfunction "-IN_2") (pintype "input"))
      (node (ref "R48") (pin "2") (pinfunction "2_2") (pintype "passive"))
      (node (ref "R49") (pin "2") (pinfunction "2_2") (pintype "passive"))
    )
    (net (code "41") (name "Net-(IC6A-OUT)") (class "Default")
      (node (ref "IC6") (pin "1") (pinfunction "OUT_1") (pintype "output"))
      (node (ref "R47") (pin "2") (pinfunction "2_2") (pintype "passive"))
      (node (ref "R48") (pin "1") (pinfunction "1_1") (pintype "passive"))
    )
    (net (code "42") (name "Net-(IC6B-+IN)") (class "Default")
      (node (ref "C27") (pin "1") (pinfunction "1_1") (pintype "passive"))
      (node (ref "IC6") (pin "5") (pinfunction "+IN_5") (pintype "input"))
      (node (ref "R46") (pin "1") (pinfunction "1_1") (pintype "passive"))
    )
    (net (code "43") (name "Net-(IC7A-+IN)") (class "Default")
      (node (ref "C18") (pin "2") (pinfunction "2_2") (pintype "passive"))
      (node (ref "IC7") (pin "3") (pinfunction "+IN_3") (pintype "input"))
      (node (ref "IC7") (pin "6") (pinfunction "-IN_6") (pintype "input"))
      (node (ref "IC7") (pin "7") (pinfunction "OUT_7") (pintype "output"))
    )
    (net (code "44") (name "Net-(IC7A--IN)") (class "Default")
      (node (ref "IC7") (pin "2") (pinfunction "-IN_2") (pintype "input"))
      (node (ref "R38") (pin "2") (pinfunction "2_2") (pintype "passive"))
      (node (ref "R39") (pin "2") (pinfunction "2_2") (pintype "passive"))
    )
    (net (code "45") (name "Net-(IC7A-OUT)") (class "Default")
      (node (ref "IC7") (pin "1") (pinfunction "OUT_1") (pintype "output"))
      (node (ref "R37") (pin "2") (pinfunction "2_2") (pintype "passive"))
      (node (ref "R38") (pin "1") (pinfunction "1_1") (pintype "passive"))
    )
    (net (code "46") (name "Net-(IC7B-+IN)") (class "Default")
      (node (ref "C17") (pin "1") (pinfunction "1_1") (pintype "passive"))
      (node (ref "IC7") (pin "5") (pinfunction "+IN_5") (pintype "input"))
      (node (ref "R36") (pin "1") (pinfunction "1_1") (pintype "passive"))
    )
    (net (code "47") (name "Net-(IC8A-+IN)") (class "Default")
      (node (ref "C22") (pin "2") (pinfunction "2_2") (pintype "passive"))
      (node (ref "IC8") (pin "3") (pinfunction "+IN_3") (pintype "input"))
      (node (ref "IC8") (pin "6") (pinfunction "-IN_6") (pintype "input"))
      (node (ref "IC8") (pin "7") (pinfunction "OUT_7") (pintype "output"))
    )
    (net (code "48") (name "Net-(IC8A--IN)") (class "Default")
      (node (ref "IC8") (pin "2") (pinfunction "-IN_2") (pintype "input"))
      (node (ref "R43") (pin "2") (pinfunction "2_2") (pintype "passive"))
      (node (ref "R44") (pin "2") (pinfunction "2_2") (pintype "passive"))
    )
    (net (code "49") (name "Net-(IC8A-OUT)") (class "Default")
      (node (ref "IC8") (pin "1") (pinfunction "OUT_1") (pintype "output"))
      (node (ref "R42") (pin "2") (pinfunction "2_2") (pintype "passive"))
      (node (ref "R43") (pin "1") (pinfunction "1_1") (pintype "passive"))
    )
    (net (code "50") (name "Net-(IC8B-+IN)") (class "Default")
      (node (ref "C21") (pin "1") (pinfunction "1_1") (pintype "passive"))
      (node (ref "IC8") (pin "5") (pinfunction "+IN_5") (pintype "input"))
      (node (ref "R41") (pin "1") (pinfunction "1_1") (pintype "passive"))
    )
    (net (code "51") (name "Net-(IC9A-+IN)") (class "Default")
      (node (ref "C32") (pin "2") (pinfunction "2_2") (pintype "passive"))
      (node (ref "IC9") (pin "3") (pinfunction "+IN_3") (pintype "input"))
      (node (ref "IC9") (pin "6") (pinfunction "-IN_6") (pintype "input"))
      (node (ref "IC9") (pin "7") (pinfunction "OUT_7") (pintype "output"))
    )
    (net (code "52") (name "Net-(IC9A--IN)") (class "Default")
      (node (ref "IC9") (pin "2") (pinfunction "-IN_2") (pintype "input"))
      (node (ref "R54") (pin "2") (pinfunction "2_2") (pintype "passive"))
      (node (ref "R55") (pin "2") (pinfunction "2_2") (pintype "passive"))
    )
    (net (code "53") (name "Net-(IC9A-OUT)") (class "Default")
      (node (ref "IC9") (pin "1") (pinfunction "OUT_1") (pintype "output"))
      (node (ref "R53") (pin "2") (pinfunction "2_2") (pintype "passive"))
      (node (ref "R54") (pin "1") (pinfunction "1_1") (pintype "passive"))
    )
    (net (code "54") (name "Net-(IC9B-+IN)") (class "Default")
      (node (ref "C31") (pin "1") (pinfunction "1_1") (pintype "passive"))
      (node (ref "IC9") (pin "5") (pinfunction "+IN_5") (pintype "input"))
      (node (ref "R52") (pin "1") (pinfunction "1_1") (pintype "passive"))
    )
    (net (code "55") (name "Net-(J1-3)") (class "Default")
      (node (ref "J1") (pin "P3") (pinfunction "3_P3") (pintype "passive"))
      (node (ref "R2") (pin "1") (pinfunction "1_1") (pintype "passive"))
      (node (ref "R3") (pin "2") (pinfunction "2_2") (pintype "passive"))
      (node (ref "T1") (pin "1") (pinfunction "C_1") (pintype "passive"))
    )
    (net (code "56") (name "Net-(J2-3)") (class "Default")
      (node (ref "J2") (pin "P3") (pinfunction "3_P3") (pintype "passive"))
      (node (ref "R4") (pin "1") (pinfunction "1_1") (pintype "passive"))
    )
    (net (code "57") (name "Net-(J3-3)") (class "Default")
      (node (ref "J3") (pin "P3") (pinfunction "3_P3") (pintype "passive"))
      (node (ref "R8") (pin "2") (pinfunction "2_2") (pintype "passive"))
    )
    (net (code "58") (name "Net-(J4-3)") (class "Default")
      (node (ref "J4") (pin "P3") (pinfunction "3_P3") (pintype "passive"))
      (node (ref "R47") (pin "1") (pinfunction "1_1") (pintype "passive"))
    )
    (net (code "59") (name "Net-(J5-3)") (class "Default")
      (node (ref "J5") (pin "P3") (pinfunction "3_P3") (pintype "passive"))
      (node (ref "R37") (pin "1") (pinfunction "1_1") (pintype "passive"))
    )
    (net (code "60") (name "Net-(J6-3)") (class "Default")
      (node (ref "J6") (pin "P3") (pinfunction "3_P3") (pintype "passive"))
      (node (ref "R42") (pin "1") (pinfunction "1_1") (pintype "passive"))
    )
    (net (code "61") (name "Net-(J7-3)") (class "Default")
      (node (ref "J7") (pin "P3") (pinfunction "3_P3") (pintype "passive"))
      (node (ref "R53") (pin "1") (pinfunction "1_1") (pintype "passive"))
    )
    (net (code "62") (name "Net-(J9-3)") (class "Default")
      (node (ref "J9") (pin "P3") (pinfunction "3_P3") (pintype "passive"))
      (node (ref "R19") (pin "1") (pinfunction "1_1") (pintype "passive"))
      (node (ref "R20") (pin "2") (pinfunction "2_2") (pintype "passive"))
      (node (ref "T4") (pin "1") (pinfunction "C_1") (pintype "passive"))
    )
    (net (code "63") (name "Net-(J13-3)") (class "Default")
      (node (ref "J13") (pin "P3") (pinfunction "3_P3") (pintype "passive"))
      (node (ref "R16") (pin "2") (pinfunction "2_2") (pintype "passive"))
    )
    (net (code "64") (name "Net-(J14-3)") (class "Default")
      (node (ref "J14") (pin "P3") (pinfunction "3_P3") (pintype "passive"))
      (node (ref "R21") (pin "1") (pinfunction "1_1") (pintype "passive"))
    )
    (net (code "65") (name "Net-(J29-3)") (class "Default")
      (node (ref "J29") (pin "P3") (pinfunction "3_P3") (pintype "passive"))
      (node (ref "R28") (pin "2") (pinfunction "2_2") (pintype "passive"))
    )
    (net (code "66") (name "Net-(J32-3)") (class "Default")
      (node (ref "J32") (pin "P3") (pinfunction "3_P3") (pintype "passive"))
      (node (ref "R31") (pin "2") (pinfunction "2_2") (pintype "passive"))
    )
    (net (code "67") (name "Net-(T1-B)") (class "Default")
      (node (ref "R1") (pin "2") (pinfunction "2_2") (pintype "passive"))
      (node (ref "T1") (pin "2") (pinfunction "B_2") (pintype "passive"))
    )
    (net (code "68") (name "Net-(T2-B)") (class "Default")
      (node (ref "R4") (pin "2") (pinfunction "2_2") (pintype "passive"))
      (node (ref "T2") (pin "2") (pinfunction "B_2") (pintype "passive"))
    )
    (net (code "69") (name "Net-(T4-B)") (class "Default")
      (node (ref "R18") (pin "2") (pinfunction "2_2") (pintype "passive"))
      (node (ref "T4") (pin "2") (pinfunction "B_2") (pintype "passive"))
    )
    (net (code "70") (name "Net-(T5-B)") (class "Default")
      (node (ref "R21") (pin "2") (pinfunction "2_2") (pintype "passive"))
      (node (ref "T5") (pin "2") (pinfunction "B_2") (pintype "passive"))
    )
    (net (code "71") (name "RDY") (class "Default")
      (node (ref "IC11") (pin "5") (pinfunction "RDY_5") (pintype "output"))
    )
    (net (code "72") (name "RX") (class "Default")
      (node (ref "J8") (pin "1") (pinfunction "1_1") (pintype "passive"))
      (node (ref "U$4") (pin "0") (pinfunction "0/RX1/T_0") (pintype "bidirectional"))
    )
    (net (code "73") (name "SCL") (class "Default")
      (node (ref "IC11") (pin "2") (pinfunction "SCL_2") (pintype "bidirectional"))
      (node (ref "R26") (pin "1") (pinfunction "1_1") (pintype "passive"))
      (node (ref "U$4") (pin "19/A5") (pinfunction "19/A5/T/SCL0_19/A5") (pintype "bidirectional"))
    )
    (net (code "74") (name "SDA") (class "Default")
      (node (ref "IC11") (pin "3") (pinfunction "SDA_3") (pintype "bidirectional"))
      (node (ref "R25") (pin "1") (pinfunction "1_1") (pintype "passive"))
      (node (ref "U$4") (pin "18/A4") (pinfunction "18/A4/T/SDA0_18/A4") (pintype "bidirectional"))
    )
    (net (code "75") (name "TX") (class "Default")
      (node (ref "J8") (pin "2") (pinfunction "2_2") (pintype "passive"))
      (node (ref "U$4") (pin "1") (pinfunction "1/TX1/T_1") (pintype "bidirectional"))
    )
    (net (code "76") (name "VCC") (class "Default")
      (node (ref "C19") (pin "1") (pinfunction "1_1") (pintype "passive"))
      (node (ref "C24") (pin "1") (pinfunction "1_1") (pintype "passive"))
      (node (ref "C29") (pin "1") (pinfunction "1_1") (pintype "passive"))
      (node (ref "C3") (pin "+") (pinfunction "+_+") (pintype "passive"))
      (node (ref "C33") (pin "1") (pinfunction "1_1") (pintype "passive"))
      (node (ref "C7") (pin "+") (pinfunction "+_+") (pintype "passive"))
      (node (ref "D1") (pin "C") (pinfunction "C_C") (pintype "passive"))
      (node (ref "IC4") (pin "3") (pinfunction "IN_3") (pintype "input"))
      (node (ref "IC6") (pin "8") (pinfunction "V+_8") (pintype "power_in"))
      (node (ref "IC7") (pin "8") (pinfunction "V+_8") (pintype "power_in"))
      (node (ref "IC8") (pin "8") (pinfunction "V+_8") (pintype "power_in"))
      (node (ref "IC9") (pin "8") (pinfunction "V+_8") (pintype "power_in"))
      (node (ref "R19") (pin "2") (pinfunction "2_2") (pintype "passive"))
      (node (ref "R2") (pin "2") (pinfunction "2_2") (pintype "passive"))
    )
    (net (code "77") (name "VEE") (class "Default")
      (node (ref "C20") (pin "2") (pinfunction "2_2") (pintype "passive"))
      (node (ref "C26") (pin "2") (pinfunction "2_2") (pintype "passive"))
      (node (ref "C30") (pin "2") (pinfunction "2_2") (pintype "passive"))
      (node (ref "C34") (pin "2") (pinfunction "2_2") (pintype "passive"))
      (node (ref "C8") (pin "-") (pinfunction "-_-") (pintype "passive"))
      (node (ref "D2") (pin "A") (pinfunction "A_A") (pintype "passive"))
      (node (ref "IC6") (pin "4") (pinfunction "V-_4") (pintype "power_in"))
      (node (ref "IC7") (pin "4") (pinfunction "V-_4") (pintype "power_in"))
      (node (ref "IC8") (pin "4") (pinfunction "V-_4") (pintype "power_in"))
      (node (ref "IC9") (pin "4") (pinfunction "V-_4") (pintype "power_in"))
      (node (ref "R14") (pin "1") (pinfunction "1_1") (pintype "passive"))
    )
    (net (code "78") (name "unconnected-(J1-2-PadP2)") (class "Default")
      (node (ref "J1") (pin "P2") (pinfunction "2_P2") (pintype "passive"))
    )
    (net (code "79") (name "unconnected-(J4-2-PadP2)") (class "Default")
      (node (ref "J4") (pin "P2") (pinfunction "2_P2") (pintype "passive"))
    )
    (net (code "80") (name "unconnected-(J5-2-PadP2)") (class "Default")
      (node (ref "J5") (pin "P2") (pinfunction "2_P2") (pintype "passive"))
    )
    (net (code "81") (name "unconnected-(J6-2-PadP2)") (class "Default")
      (node (ref "J6") (pin "P2") (pinfunction "2_P2") (pintype "passive"))
    )
    (net (code "82") (name "unconnected-(J7-2-PadP2)") (class "Default")
      (node (ref "J7") (pin "P2") (pinfunction "2_P2") (pintype "passive"))
    )
    (net (code "83") (name "unconnected-(J9-2-PadP2)") (class "Default")
      (node (ref "J9") (pin "P2") (pinfunction "2_P2") (pintype "passive"))
    )
    (net (code "84") (name "~{LDAC}") (class "Default")
      (node (ref "IC11") (pin "4") (pinfunction "~{LDAC}_4") (pintype "input"))
      (node (ref "R50") (pin "2") (pinfunction "2_2") (pintype "passive"))
    )
  )
)
